# Main.net
KiCad netlist of a schematic drawn in Altium Designer
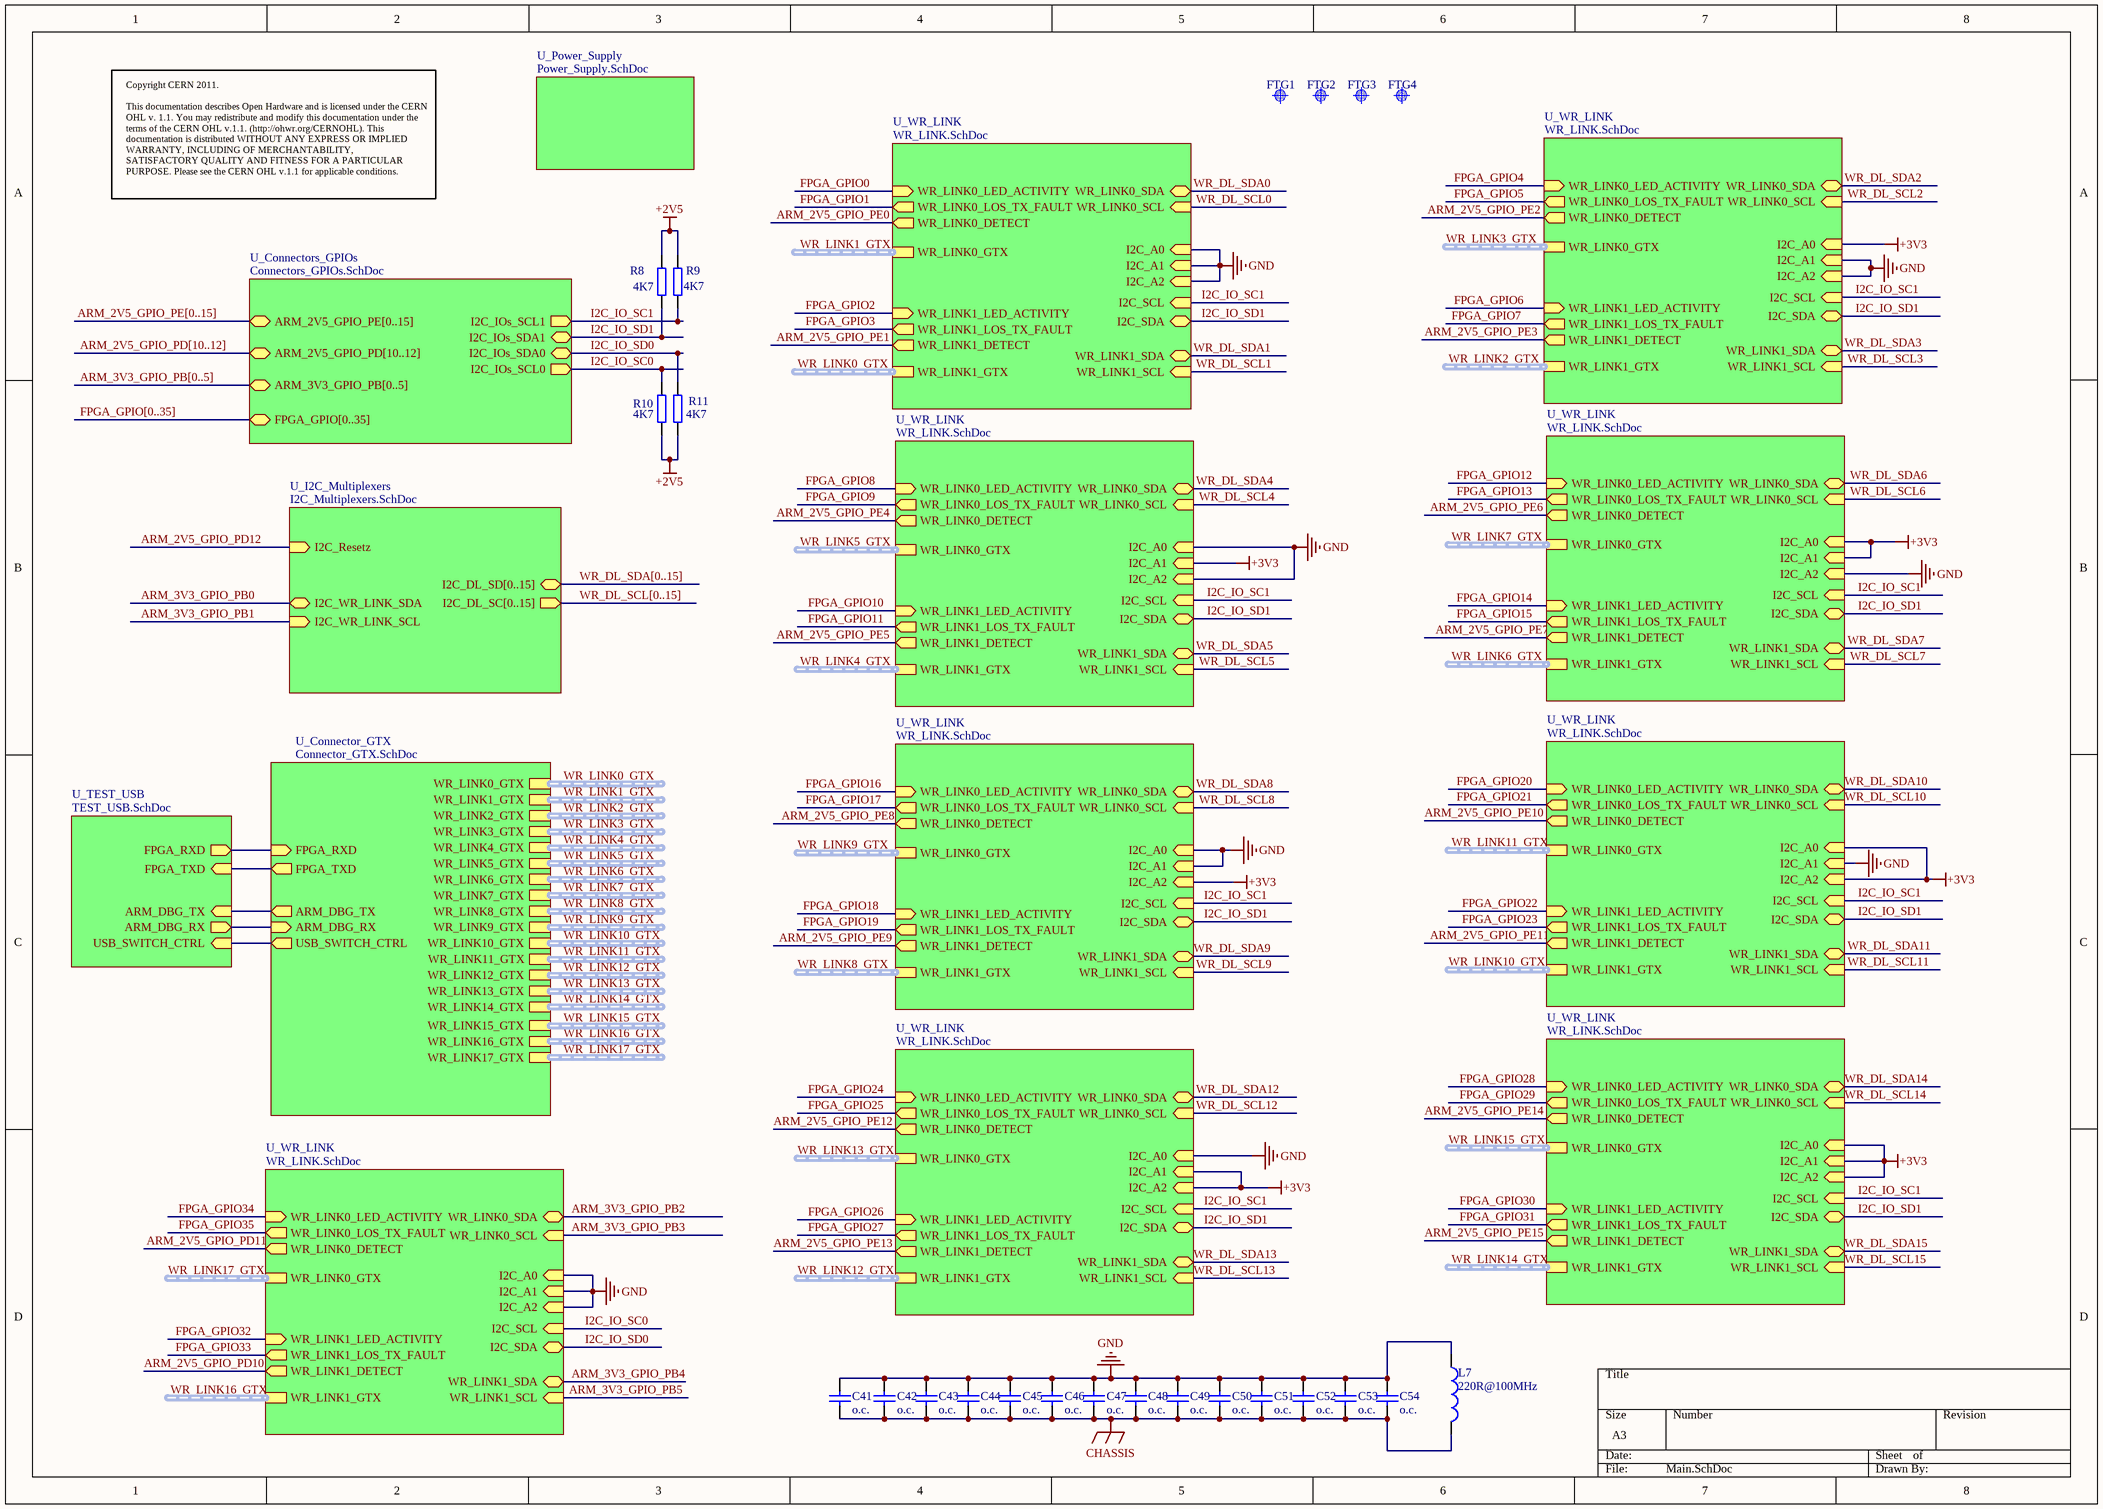
[diagram p0: Main.SchDoc]

(export (version "E")
  (design (tool "Eeschema 10.0.6"))
  (components
    (comp (ref "C41")
      (value "o.c.")
      (footprint "CC1608-0603")
      (description "Capacitor")
      (fields
        (field (name "TOLERANCE") "±10%")
        (field (name "VOLTAGE") "16V")
        (field (name "PUBLISHER") "Altium Limited")
      )
      (libsource (lib "wr_switch") (part "Cap"))
    )
    (comp (ref "C42")
      (value "o.c.")
      (footprint "CC1608-0603")
      (description "Capacitor")
      (fields
        (field (name "TOLERANCE") "±10%")
        (field (name "VOLTAGE") "16V")
        (field (name "PUBLISHER") "Altium Limited")
      )
      (libsource (lib "wr_switch") (part "Cap"))
    )
    (comp (ref "C43")
      (value "o.c.")
      (footprint "CC1608-0603")
      (description "Capacitor")
      (fields
        (field (name "TOLERANCE") "±10%")
        (field (name "VOLTAGE") "16V")
        (field (name "PUBLISHER") "Altium Limited")
      )
      (libsource (lib "wr_switch") (part "Cap"))
    )
    (comp (ref "C44")
      (value "o.c.")
      (footprint "CC1608-0603")
      (description "Capacitor")
      (fields
        (field (name "TOLERANCE") "±10%")
        (field (name "VOLTAGE") "16V")
        (field (name "PUBLISHER") "Altium Limited")
      )
      (libsource (lib "wr_switch") (part "Cap"))
    )
    (comp (ref "C45")
      (value "o.c.")
      (footprint "CC1608-0603")
      (description "Capacitor")
      (fields
        (field (name "TOLERANCE") "±10%")
        (field (name "VOLTAGE") "16V")
        (field (name "PUBLISHER") "Altium Limited")
      )
      (libsource (lib "wr_switch") (part "Cap"))
    )
    (comp (ref "C46")
      (value "o.c.")
      (footprint "CC1608-0603")
      (description "Capacitor")
      (fields
        (field (name "TOLERANCE") "±10%")
        (field (name "VOLTAGE") "16V")
        (field (name "PUBLISHER") "Altium Limited")
      )
      (libsource (lib "wr_switch") (part "Cap"))
    )
    (comp (ref "C47")
      (value "o.c.")
      (footprint "CC1608-0603")
      (description "Capacitor")
      (fields
        (field (name "TOLERANCE") "±10%")
        (field (name "VOLTAGE") "16V")
        (field (name "PUBLISHER") "Altium Limited")
      )
      (libsource (lib "wr_switch") (part "Cap"))
    )
    (comp (ref "C48")
      (value "o.c.")
      (footprint "CC1608-0603")
      (description "Capacitor")
      (fields
        (field (name "TOLERANCE") "±10%")
        (field (name "VOLTAGE") "16V")
        (field (name "PUBLISHER") "Altium Limited")
      )
      (libsource (lib "wr_switch") (part "Cap"))
    )
    (comp (ref "C49")
      (value "o.c.")
      (footprint "CC1608-0603")
      (description "Capacitor")
      (fields
        (field (name "TOLERANCE") "±10%")
        (field (name "VOLTAGE") "16V")
        (field (name "PUBLISHER") "Altium Limited")
      )
      (libsource (lib "wr_switch") (part "Cap"))
    )
    (comp (ref "C50")
      (value "o.c.")
      (footprint "CC1608-0603")
      (description "Capacitor")
      (fields
        (field (name "TOLERANCE") "±10%")
        (field (name "VOLTAGE") "16V")
        (field (name "PUBLISHER") "Altium Limited")
      )
      (libsource (lib "wr_switch") (part "Cap"))
    )
    (comp (ref "C51")
      (value "o.c.")
      (footprint "CC1608-0603")
      (description "Capacitor")
      (fields
        (field (name "TOLERANCE") "±10%")
        (field (name "VOLTAGE") "16V")
        (field (name "PUBLISHER") "Altium Limited")
      )
      (libsource (lib "wr_switch") (part "Cap"))
    )
    (comp (ref "C52")
      (value "o.c.")
      (footprint "CC1608-0603")
      (description "Capacitor")
      (fields
        (field (name "TOLERANCE") "±10%")
        (field (name "VOLTAGE") "16V")
        (field (name "PUBLISHER") "Altium Limited")
      )
      (libsource (lib "wr_switch") (part "Cap"))
    )
    (comp (ref "C53")
      (value "o.c.")
      (footprint "CC1608-0603")
      (description "Capacitor")
      (fields
        (field (name "TOLERANCE") "±10%")
        (field (name "VOLTAGE") "16V")
        (field (name "PUBLISHER") "Altium Limited")
      )
      (libsource (lib "wr_switch") (part "Cap"))
    )
    (comp (ref "C54")
      (value "o.c.")
      (footprint "CC1608-0603")
      (description "Capacitor")
      (fields
        (field (name "TOLERANCE") "±10%")
        (field (name "VOLTAGE") "16V")
        (field (name "PUBLISHER") "Altium Limited")
      )
      (libsource (lib "wr_switch") (part "Cap"))
    )
    (comp (ref "FTG1")
      (value "Use only in PCB")
      (footprint "FIDUCIAL_TOP_S100-200")
      (description "Fiducial Target")
      (fields (field (name "PART NUMBER") "FIDUCIAL_TARGET_S100-200") (field (name "AUTHOR") "CERN DEM JLC"))
      (libsource (lib "wr_switch") (part "Fiducial Target"))
    )
    (comp (ref "FTG2")
      (value "Use only in PCB")
      (footprint "FIDUCIAL_TOP_S100-200")
      (description "Fiducial Target")
      (fields (field (name "PART NUMBER") "FIDUCIAL_TARGET_S100-200") (field (name "AUTHOR") "CERN DEM JLC"))
      (libsource (lib "wr_switch") (part "Fiducial Target"))
    )
    (comp (ref "FTG3")
      (value "Use only in PCB")
      (footprint "FIDUCIAL_TOP_S100-200")
      (description "Fiducial Target")
      (fields (field (name "PART NUMBER") "FIDUCIAL_TARGET_S100-200") (field (name "AUTHOR") "CERN DEM JLC"))
      (libsource (lib "wr_switch") (part "Fiducial Target"))
    )
    (comp (ref "FTG4")
      (value "Use only in PCB")
      (footprint "FIDUCIAL_TOP_S100-200")
      (description "Fiducial Target")
      (fields (field (name "PART NUMBER") "FIDUCIAL_TARGET_S100-200") (field (name "AUTHOR") "CERN DEM JLC"))
      (libsource (lib "wr_switch") (part "Fiducial Target"))
    )
    (comp (ref "L7")
      (value "220R@100MHz Ferrite Bead")
      (footprint "0603")
      (description "ferrite bead")
      (fields (field (name "IMPEDANCE") "220R@100MHz"))
      (libsource (lib "wr_switch") (part "L_FERRITE_BEAD"))
    )
    (comp (ref "R8")
      (value "4K7")
      (footprint "0603")
      (description "SMD Resistor")
      (fields (field (name "TOLERANCE") "±1%"))
      (libsource (lib "wr_switch") (part "RES_SMD"))
    )
    (comp (ref "R9")
      (value "4K7")
      (footprint "0603")
      (description "SMD Resistor")
      (fields (field (name "TOLERANCE") "±1%"))
      (libsource (lib "wr_switch") (part "RES_SMD"))
    )
    (comp (ref "R10")
      (value "4K7")
      (footprint "0603")
      (description "SMD Resistor")
      (fields (field (name "TOLERANCE") "±1%"))
      (libsource (lib "wr_switch") (part "RES_SMD"))
    )
    (comp (ref "R11")
      (value "4K7")
      (footprint "0603")
      (description "SMD Resistor")
      (fields (field (name "TOLERANCE") "±1%"))
      (libsource (lib "wr_switch") (part "RES_SMD"))
    )
  )
  (nets
    (net (code "19") (name "+2V5") (class "Default")
      (node (ref "R10") (pin "2") (pinfunction "2_2") (pintype "passive"))
      (node (ref "R11") (pin "1") (pinfunction "1_1") (pintype "passive"))
      (node (ref "R8") (pin "2") (pinfunction "2_2") (pintype "passive"))
      (node (ref "R9") (pin "1") (pinfunction "1_1") (pintype "passive"))
    )
    (net (code "96") (name "/I2C_IO_SC0") (class "Default")
      (node (ref "R10") (pin "1") (pinfunction "1_1") (pintype "passive"))
    )
    (net (code "97") (name "/I2C_IO_SC1") (class "Default")
      (node (ref "R9") (pin "2") (pinfunction "2_2") (pintype "passive"))
    )
    (net (code "98") (name "/I2C_IO_SD0") (class "Default")
      (node (ref "R11") (pin "2") (pinfunction "2_2") (pintype "passive"))
    )
    (net (code "99") (name "/I2C_IO_SD1") (class "Default")
      (node (ref "R8") (pin "1") (pinfunction "1_1") (pintype "passive"))
    )
    (net (code "181") (name "CHASSIS") (class "Default")
      (node (ref "C41") (pin "1") (pinfunction "1_1") (pintype "passive"))
      (node (ref "C42") (pin "1") (pinfunction "1_1") (pintype "passive"))
      (node (ref "C43") (pin "1") (pinfunction "1_1") (pintype "passive"))
      (node (ref "C44") (pin "1") (pinfunction "1_1") (pintype "passive"))
      (node (ref "C45") (pin "1") (pinfunction "1_1") (pintype "passive"))
      (node (ref "C46") (pin "1") (pinfunction "1_1") (pintype "passive"))
      (node (ref "C47") (pin "1") (pinfunction "1_1") (pintype "passive"))
      (node (ref "C48") (pin "1") (pinfunction "1_1") (pintype "passive"))
      (node (ref "C49") (pin "1") (pinfunction "1_1") (pintype "passive"))
      (node (ref "C50") (pin "1") (pinfunction "1_1") (pintype "passive"))
      (node (ref "C51") (pin "1") (pinfunction "1_1") (pintype "passive"))
      (node (ref "C52") (pin "1") (pinfunction "1_1") (pintype "passive"))
      (node (ref "C53") (pin "1") (pinfunction "1_1") (pintype "passive"))
      (node (ref "C54") (pin "1") (pinfunction "1_1") (pintype "passive"))
      (node (ref "L7") (pin "2") (pinfunction "2_2") (pintype "passive"))
    )
    (net (code "182") (name "GND") (class "Default")
      (node (ref "C41") (pin "2") (pinfunction "2_2") (pintype "passive"))
      (node (ref "C42") (pin "2") (pinfunction "2_2") (pintype "passive"))
      (node (ref "C43") (pin "2") (pinfunction "2_2") (pintype "passive"))
      (node (ref "C44") (pin "2") (pinfunction "2_2") (pintype "passive"))
      (node (ref "C45") (pin "2") (pinfunction "2_2") (pintype "passive"))
      (node (ref "C46") (pin "2") (pinfunction "2_2") (pintype "passive"))
      (node (ref "C47") (pin "2") (pinfunction "2_2") (pintype "passive"))
      (node (ref "C48") (pin "2") (pinfunction "2_2") (pintype "passive"))
      (node (ref "C49") (pin "2") (pinfunction "2_2") (pintype "passive"))
      (node (ref "C50") (pin "2") (pinfunction "2_2") (pintype "passive"))
      (node (ref "C51") (pin "2") (pinfunction "2_2") (pintype "passive"))
      (node (ref "C52") (pin "2") (pinfunction "2_2") (pintype "passive"))
      (node (ref "C53") (pin "2") (pinfunction "2_2") (pintype "passive"))
      (node (ref "C54") (pin "2") (pinfunction "2_2") (pintype "passive"))
      (node (ref "L7") (pin "1") (pinfunction "1_1") (pintype "passive"))
    )
  )
)
